# mosfet2.net
KiCad netlist of a schematic drawn in EAGLE
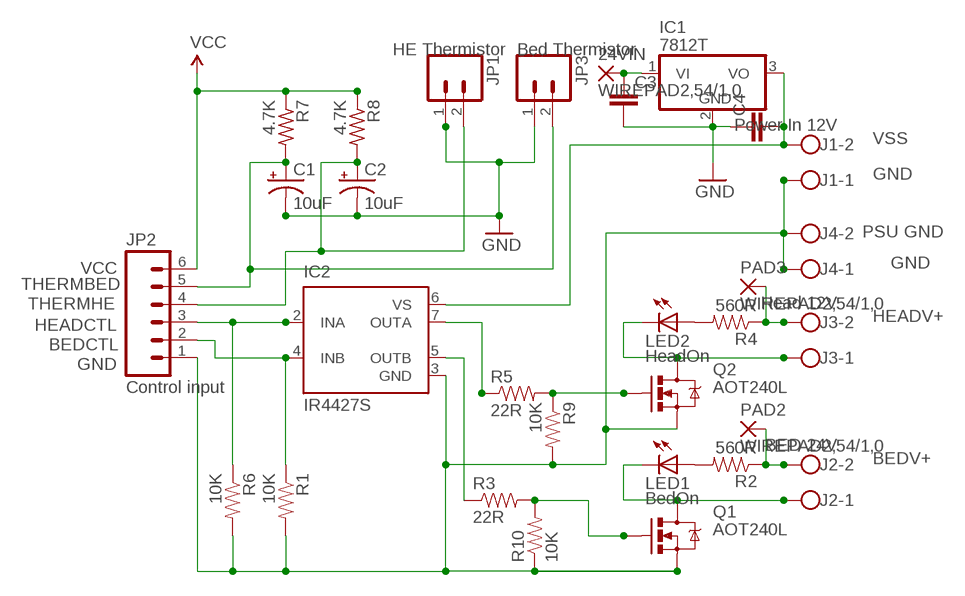
[diagram p0: schematic, sheet 1]

(export (version "E")
  (design (tool "Eeschema 10.0.6"))
  (components
    (comp (ref "24VIN")
      (value "WIREPAD2,54/1,0")
      (footprint "eagle-import:2,54_1,0")
      (libsource (lib "eagle-import") (part "WIREPAD2,54/1,0"))
    )
    (comp (ref "C1")
      (value "10uF")
      (footprint "eagle-import:CPOL-RADIAL-10UF-25V")
      (libsource (lib "eagle-import") (part "CAP_POLPTH2"))
    )
    (comp (ref "C2")
      (value "10uF")
      (footprint "eagle-import:CPOL-RADIAL-10UF-25V")
      (libsource (lib "eagle-import") (part "CAP_POLPTH2"))
    )
    (comp (ref "C3")
      (value "CAPEZ")
      (footprint "eagle-import:CAP-PTH-SMALLEZ")
      (libsource (lib "eagle-import") (part "CAPEZ"))
    )
    (comp (ref "C4")
      (value "CAPEZ")
      (footprint "eagle-import:CAP-PTH-SMALLEZ")
      (libsource (lib "eagle-import") (part "CAPEZ"))
    )
    (comp (ref "IC1")
      (value "7812T")
      (footprint "eagle-import:TO220H")
      (libsource (lib "eagle-import") (part "78T12"))
    )
    (comp (ref "IC2")
      (value "IR4427S")
      (footprint "eagle-import:SO08")
      (fields (field (name "MF") "INTERNATIONAL RECTIFIER(IR)") (field (name "MPN") "IR4427STRPBF"))
      (libsource (lib "eagle-import") (part "IR4427S"))
    )
    (comp (ref "J1")
      (value "Power In 12V")
      (footprint "eagle-import:W237-102")
      (fields (field (name "MPN") "237-102"))
      (libsource (lib "eagle-import") (part "W237-102"))
    )
    (comp (ref "J2")
      (value "BED 24V")
      (footprint "eagle-import:W237-102")
      (fields (field (name "MPN") "237-102"))
      (libsource (lib "eagle-import") (part "W237-102"))
    )
    (comp (ref "J3")
      (value "Head 12V")
      (footprint "eagle-import:W237-102")
      (fields
        (field (name "MPN") "237-102")
        (field (name "MPN_1") "237-102")
        (field (name "OC_FARNELL") "unknown")
        (field (name "OC_NEWARK") "70K9898")
      )
      (libsource (lib "eagle-import") (part "W237-102"))
    )
    (comp (ref "J4")
      (value "PSU GND")
      (footprint "eagle-import:W237-102")
      (fields (field (name "MPN") "237-102"))
      (libsource (lib "eagle-import") (part "W237-102"))
    )
    (comp (ref "JP1")
      (value "HE Thermistor")
      (footprint "eagle-import:1X02")
      (libsource (lib "eagle-import") (part "M02PTH"))
    )
    (comp (ref "JP2")
      (value "Control input")
      (footprint "eagle-import:1X06")
      (libsource (lib "eagle-import") (part "M06SIP"))
    )
    (comp (ref "JP3")
      (value "Bed Thermistor")
      (footprint "eagle-import:1X02")
      (libsource (lib "eagle-import") (part "M02PTH"))
    )
    (comp (ref "LED1")
      (value "BedOn")
      (footprint "eagle-import:LED3MM-NS")
      (libsource (lib "eagle-import") (part "LED-3MM-NO_SILK"))
    )
    (comp (ref "LED2")
      (value "HeadOn")
      (footprint "eagle-import:LED3MM-NS")
      (libsource (lib "eagle-import") (part "LED-3MM-NO_SILK"))
    )
    (comp (ref "PAD2")
      (value "WIREPAD2,54/1,0")
      (footprint "eagle-import:2,54_1,0")
      (libsource (lib "eagle-import") (part "WIREPAD2,54/1,0"))
    )
    (comp (ref "PAD3")
      (value "WIREPAD2,54/1,0")
      (footprint "eagle-import:2,54_1,0")
      (libsource (lib "eagle-import") (part "WIREPAD2,54/1,0"))
    )
    (comp (ref "Q1")
      (value "AOT240L")
      (footprint "eagle-import:TO220V")
      (libsource (lib "eagle-import") (part "MOSFET-NCHANNELPTH2"))
    )
    (comp (ref "Q2")
      (value "AOT240L")
      (footprint "eagle-import:TO220V")
      (libsource (lib "eagle-import") (part "MOSFET-NCHANNELPTH2"))
    )
    (comp (ref "R1")
      (value "10K")
      (footprint "eagle-import:AXIAL-0.4")
      (libsource (lib "eagle-import") (part "RESISTORPTH-1/4W"))
    )
    (comp (ref "R2")
      (value "560R")
      (footprint "eagle-import:AXIAL-0.4")
      (libsource (lib "eagle-import") (part "RESISTORPTH-1/4W"))
    )
    (comp (ref "R3")
      (value "22R")
      (footprint "eagle-import:AXIAL-0.4")
      (libsource (lib "eagle-import") (part "RESISTORPTH-1/4W"))
    )
    (comp (ref "R4")
      (value "560R")
      (footprint "eagle-import:AXIAL-0.4")
      (libsource (lib "eagle-import") (part "RESISTORPTH-1/4W"))
    )
    (comp (ref "R5")
      (value "22R")
      (footprint "eagle-import:AXIAL-0.4")
      (libsource (lib "eagle-import") (part "RESISTORPTH-1/4W"))
    )
    (comp (ref "R6")
      (value "10K")
      (footprint "eagle-import:AXIAL-0.4")
      (libsource (lib "eagle-import") (part "RESISTORPTH-1/4W"))
    )
    (comp (ref "R7")
      (value "4.7K")
      (footprint "eagle-import:0204_7")
      (libsource (lib "eagle-import") (part "R-US_0204/7"))
    )
    (comp (ref "R8")
      (value "4.7K")
      (footprint "eagle-import:0204_7")
      (libsource (lib "eagle-import") (part "R-US_0204/7"))
    )
    (comp (ref "R9")
      (value "10K")
      (footprint "eagle-import:AXIAL-0.4")
      (libsource (lib "eagle-import") (part "RESISTORPTH-1/4W"))
    )
    (comp (ref "R10")
      (value "10K")
      (footprint "eagle-import:AXIAL-0.4")
      (libsource (lib "eagle-import") (part "RESISTORPTH-1/4W"))
    )
  )
  (nets
    (net (code "1") (name "/BEDCTL") (class "Default")
      (node (ref "IC2") (pin "4") (pinfunction "INB_4") (pintype "input"))
      (node (ref "JP2") (pin "2") (pinfunction "2_2") (pintype "passive"))
      (node (ref "R1") (pin "P$1") (pinfunction "1_P$1") (pintype "passive"))
    )
    (net (code "2") (name "/BEDV+") (class "Default")
      (node (ref "J2") (pin "2") (pinfunction "KL_2") (pintype "passive"))
      (node (ref "PAD2") (pin "1") (pinfunction "P_1") (pintype "passive"))
      (node (ref "R2") (pin "P$1") (pinfunction "1_P$1") (pintype "passive"))
    )
    (net (code "3") (name "/HEADCTL") (class "Default")
      (node (ref "IC2") (pin "2") (pinfunction "INA_2") (pintype "input"))
      (node (ref "JP2") (pin "3") (pinfunction "3_3") (pintype "passive"))
      (node (ref "R6") (pin "P$1") (pinfunction "1_P$1") (pintype "passive"))
    )
    (net (code "4") (name "/HEADV+") (class "Default")
      (node (ref "J3") (pin "2") (pinfunction "KL_2") (pintype "passive"))
      (node (ref "PAD3") (pin "1") (pinfunction "P_1") (pintype "passive"))
      (node (ref "R4") (pin "P$1") (pinfunction "1_P$1") (pintype "passive"))
    )
    (net (code "5") (name "/THERMBED") (class "Default")
      (node (ref "C1") (pin "1") (pinfunction "+_1") (pintype "passive"))
      (node (ref "JP2") (pin "5") (pinfunction "5_5") (pintype "passive"))
      (node (ref "JP3") (pin "2") (pinfunction "2_2") (pintype "passive"))
      (node (ref "R7") (pin "2") (pinfunction "2_2") (pintype "passive"))
    )
    (net (code "6") (name "/THERMHE") (class "Default")
      (node (ref "C2") (pin "1") (pinfunction "+_1") (pintype "passive"))
      (node (ref "JP1") (pin "2") (pinfunction "2_2") (pintype "passive"))
      (node (ref "JP2") (pin "4") (pinfunction "4_4") (pintype "passive"))
      (node (ref "R8") (pin "2") (pinfunction "2_2") (pintype "passive"))
    )
    (net (code "7") (name "/VSS") (class "Default")
      (node (ref "C4") (pin "2") (pinfunction "2_2") (pintype "passive"))
      (node (ref "IC1") (pin "3") (pinfunction "VO_3") (pintype "passive"))
      (node (ref "IC2") (pin "6") (pinfunction "VS_6") (pintype "power_in"))
      (node (ref "J1") (pin "2") (pinfunction "KL_2") (pintype "passive"))
    )
    (net (code "8") (name "GND") (class "Default")
      (node (ref "C1") (pin "2") (pinfunction "-_2") (pintype "passive"))
      (node (ref "C2") (pin "2") (pinfunction "-_2") (pintype "passive"))
      (node (ref "C3") (pin "2") (pinfunction "2_2") (pintype "passive"))
      (node (ref "C4") (pin "1") (pinfunction "1_1") (pintype "passive"))
      (node (ref "IC1") (pin "2") (pinfunction "GND_2") (pintype "passive"))
      (node (ref "IC2") (pin "3") (pinfunction "GND_3") (pintype "power_in"))
      (node (ref "J1") (pin "1") (pinfunction "KL_1") (pintype "passive"))
      (node (ref "J4") (pin "1") (pinfunction "KL_1") (pintype "passive"))
      (node (ref "J4") (pin "2") (pinfunction "KL_2") (pintype "passive"))
      (node (ref "JP1") (pin "1") (pinfunction "1_1") (pintype "passive"))
      (node (ref "JP2") (pin "1") (pinfunction "1_1") (pintype "passive"))
      (node (ref "JP3") (pin "1") (pinfunction "1_1") (pintype "passive"))
      (node (ref "Q1") (pin "3") (pinfunction "S_3") (pintype "passive"))
      (node (ref "Q2") (pin "3") (pinfunction "S_3") (pintype "passive"))
      (node (ref "R1") (pin "P$2") (pinfunction "2_P$2") (pintype "passive"))
      (node (ref "R10") (pin "P$1") (pinfunction "1_P$1") (pintype "passive"))
      (node (ref "R6") (pin "P$2") (pinfunction "2_P$2") (pintype "passive"))
      (node (ref "R9") (pin "P$2") (pinfunction "2_P$2") (pintype "passive"))
    )
    (net (code "9") (name "Net-(24VIN-P)") (class "Default")
      (node (ref "24VIN") (pin "1") (pinfunction "P_1") (pintype "passive"))
      (node (ref "C3") (pin "1") (pinfunction "1_1") (pintype "passive"))
      (node (ref "IC1") (pin "1") (pinfunction "VI_1") (pintype "input"))
    )
    (net (code "10") (name "Net-(IC2-OUTA)") (class "Default")
      (node (ref "IC2") (pin "7") (pinfunction "OUTA_7") (pintype "output"))
      (node (ref "R5") (pin "P$1") (pinfunction "1_P$1") (pintype "passive"))
    )
    (net (code "11") (name "Net-(IC2-OUTB)") (class "Default")
      (node (ref "IC2") (pin "5") (pinfunction "OUTB_5") (pintype "output"))
      (node (ref "R3") (pin "P$1") (pinfunction "1_P$1") (pintype "passive"))
    )
    (net (code "12") (name "Net-(J2A-KL)") (class "Default")
      (node (ref "J2") (pin "1") (pinfunction "KL_1") (pintype "passive"))
      (node (ref "LED1") (pin "K") (pinfunction "C_K") (pintype "passive"))
      (node (ref "Q1") (pin "2") (pinfunction "D_2") (pintype "passive"))
    )
    (net (code "13") (name "Net-(J3A-KL)") (class "Default")
      (node (ref "J3") (pin "1") (pinfunction "KL_1") (pintype "passive"))
      (node (ref "LED2") (pin "K") (pinfunction "C_K") (pintype "passive"))
      (node (ref "Q2") (pin "2") (pinfunction "D_2") (pintype "passive"))
    )
    (net (code "14") (name "Net-(Q1-G)") (class "Default")
      (node (ref "Q1") (pin "1") (pinfunction "G_1") (pintype "passive"))
      (node (ref "R10") (pin "P$2") (pinfunction "2_P$2") (pintype "passive"))
      (node (ref "R3") (pin "P$2") (pinfunction "2_P$2") (pintype "passive"))
    )
    (net (code "15") (name "Net-(Q2-G)") (class "Default")
      (node (ref "Q2") (pin "1") (pinfunction "G_1") (pintype "passive"))
      (node (ref "R5") (pin "P$2") (pinfunction "2_P$2") (pintype "passive"))
      (node (ref "R9") (pin "P$1") (pinfunction "1_P$1") (pintype "passive"))
    )
    (net (code "16") (name "Net-(R2-2)") (class "Default")
      (node (ref "LED1") (pin "A") (pinfunction "A_A") (pintype "passive"))
      (node (ref "R2") (pin "P$2") (pinfunction "2_P$2") (pintype "passive"))
    )
    (net (code "17") (name "Net-(R4-2)") (class "Default")
      (node (ref "LED2") (pin "A") (pinfunction "A_A") (pintype "passive"))
      (node (ref "R4") (pin "P$2") (pinfunction "2_P$2") (pintype "passive"))
    )
    (net (code "18") (name "VCC") (class "Default")
      (node (ref "JP2") (pin "6") (pinfunction "6_6") (pintype "passive"))
      (node (ref "R7") (pin "1") (pinfunction "1_1") (pintype "passive"))
      (node (ref "R8") (pin "1") (pinfunction "1_1") (pintype "passive"))
    )
  )
)
